# split_node_02.net
KiCad netlist of a schematic drawn in EAGLE
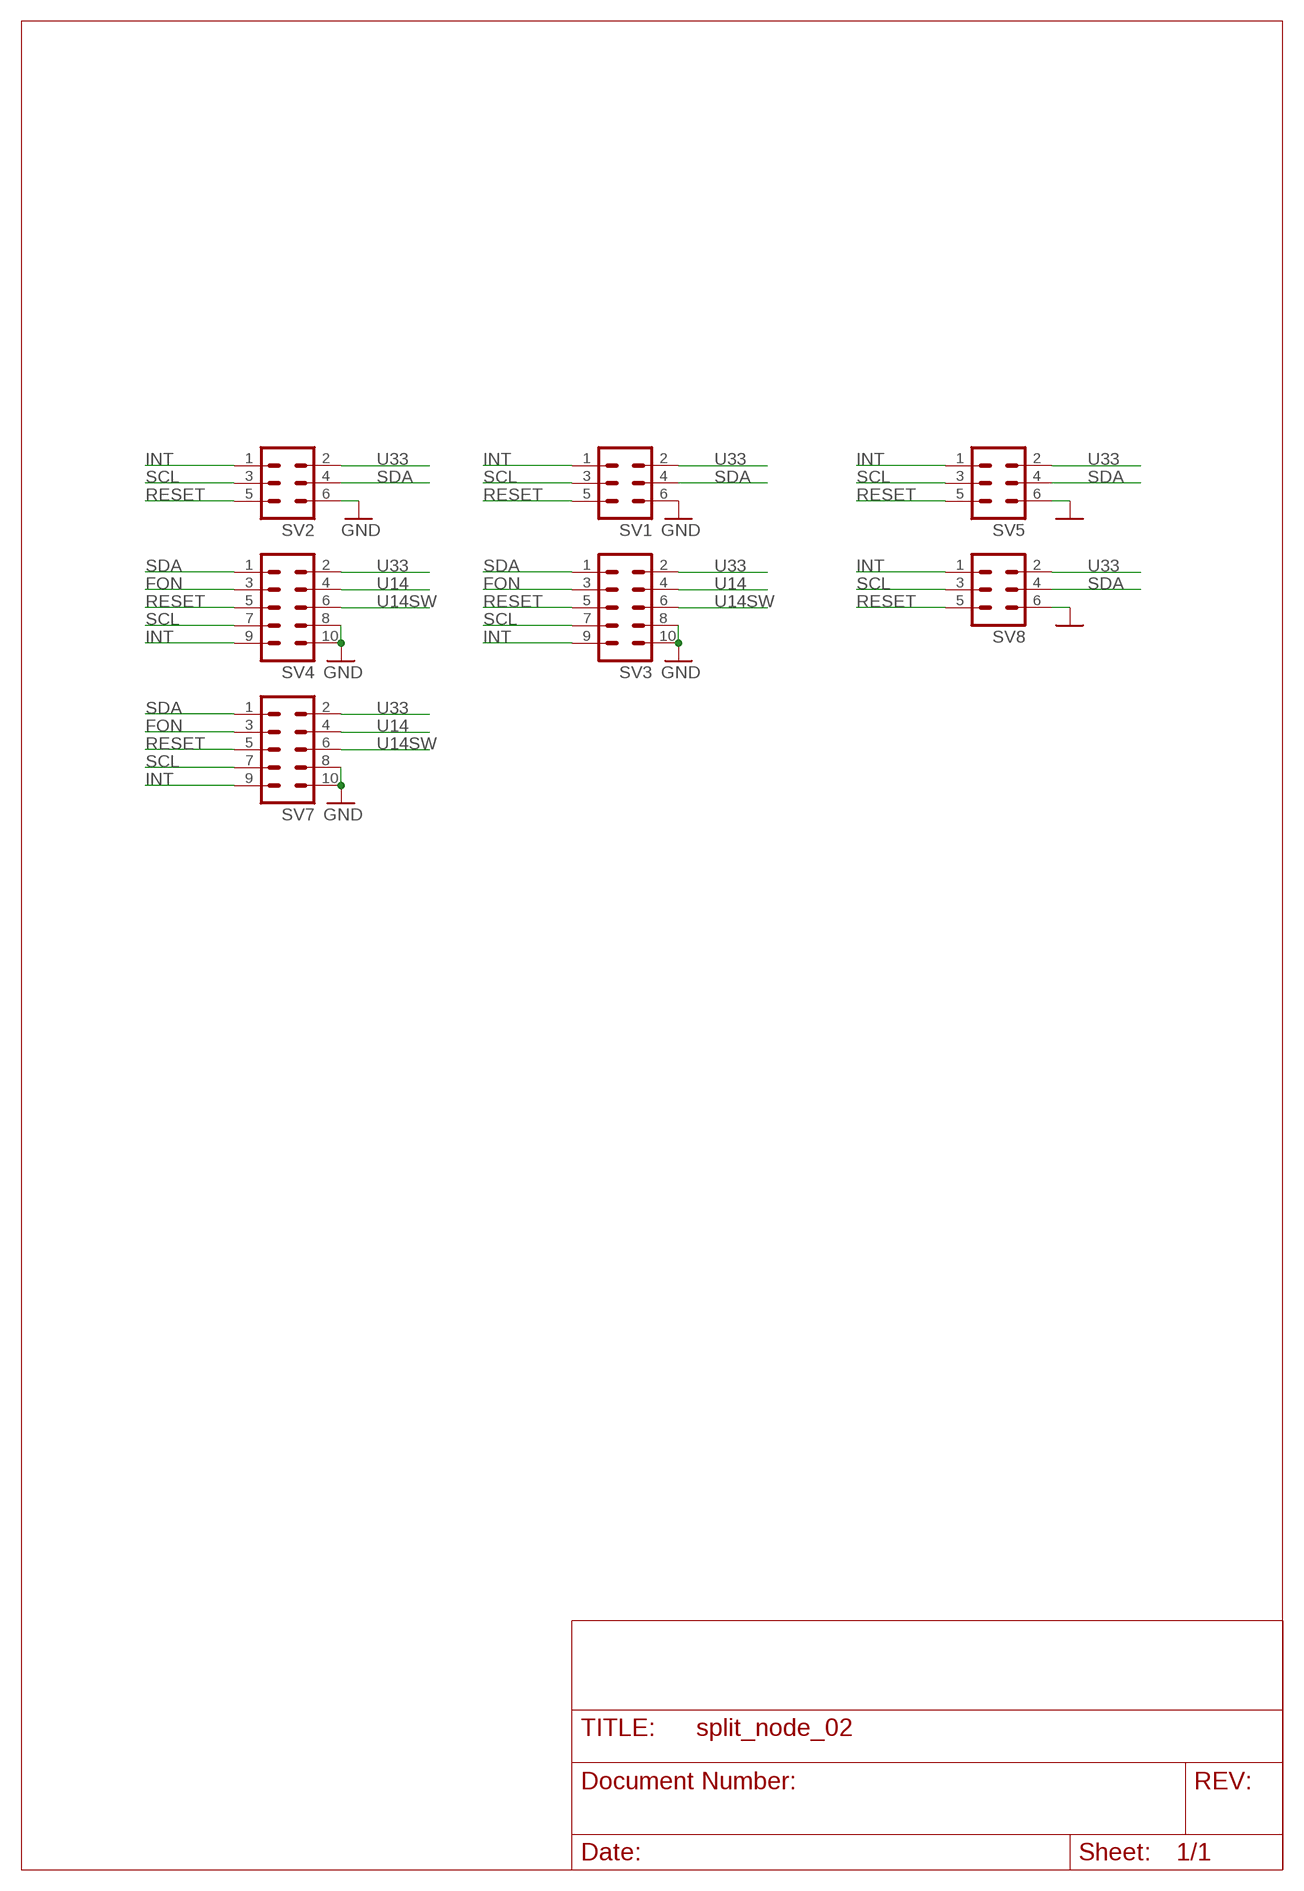
[diagram p0: schematic, sheet 1]

(export (version "E")
  (design (tool "Eeschema 10.0.6"))
  (components
    (comp (ref "SV1")
      (value "ML6")
      (footprint "eagle-import:ML6")
      (libsource (lib "eagle-import") (part "ML6"))
    )
    (comp (ref "SV2")
      (value "ML6")
      (footprint "eagle-import:ML6")
      (libsource (lib "eagle-import") (part "ML6"))
    )
    (comp (ref "SV3")
      (value "ML10")
      (footprint "eagle-import:ML10")
      (libsource (lib "eagle-import") (part "ML10"))
    )
    (comp (ref "SV4")
      (value "ML10")
      (footprint "eagle-import:ML10")
      (libsource (lib "eagle-import") (part "ML10"))
    )
    (comp (ref "SV5")
      (value "ML6")
      (footprint "eagle-import:ML6")
      (libsource (lib "eagle-import") (part "ML6"))
    )
    (comp (ref "SV7")
      (value "ML10")
      (footprint "eagle-import:ML10")
      (libsource (lib "eagle-import") (part "ML10"))
    )
    (comp (ref "SV8")
      (value "ML6")
      (footprint "eagle-import:ML6")
      (libsource (lib "eagle-import") (part "ML6"))
    )
  )
  (nets
    (net (code "1") (name "/FON") (class "Default")
      (node (ref "SV3") (pin "3") (pinfunction "3_3") (pintype "passive"))
      (node (ref "SV4") (pin "3") (pinfunction "3_3") (pintype "passive"))
      (node (ref "SV7") (pin "3") (pinfunction "3_3") (pintype "passive"))
    )
    (net (code "2") (name "/INT") (class "Default")
      (node (ref "SV1") (pin "1") (pinfunction "1_1") (pintype "passive"))
      (node (ref "SV2") (pin "1") (pinfunction "1_1") (pintype "passive"))
      (node (ref "SV3") (pin "9") (pinfunction "9_9") (pintype "passive"))
      (node (ref "SV4") (pin "9") (pinfunction "9_9") (pintype "passive"))
      (node (ref "SV5") (pin "1") (pinfunction "1_1") (pintype "passive"))
      (node (ref "SV7") (pin "9") (pinfunction "9_9") (pintype "passive"))
      (node (ref "SV8") (pin "1") (pinfunction "1_1") (pintype "passive"))
    )
    (net (code "3") (name "/RESET") (class "Default")
      (node (ref "SV1") (pin "5") (pinfunction "5_5") (pintype "passive"))
      (node (ref "SV2") (pin "5") (pinfunction "5_5") (pintype "passive"))
      (node (ref "SV3") (pin "5") (pinfunction "5_5") (pintype "passive"))
      (node (ref "SV4") (pin "5") (pinfunction "5_5") (pintype "passive"))
      (node (ref "SV5") (pin "5") (pinfunction "5_5") (pintype "passive"))
      (node (ref "SV7") (pin "5") (pinfunction "5_5") (pintype "passive"))
      (node (ref "SV8") (pin "5") (pinfunction "5_5") (pintype "passive"))
    )
    (net (code "4") (name "/SCL") (class "Default")
      (node (ref "SV1") (pin "3") (pinfunction "3_3") (pintype "passive"))
      (node (ref "SV2") (pin "3") (pinfunction "3_3") (pintype "passive"))
      (node (ref "SV3") (pin "7") (pinfunction "7_7") (pintype "passive"))
      (node (ref "SV4") (pin "7") (pinfunction "7_7") (pintype "passive"))
      (node (ref "SV5") (pin "3") (pinfunction "3_3") (pintype "passive"))
      (node (ref "SV7") (pin "7") (pinfunction "7_7") (pintype "passive"))
      (node (ref "SV8") (pin "3") (pinfunction "3_3") (pintype "passive"))
    )
    (net (code "5") (name "/SDA") (class "Default")
      (node (ref "SV1") (pin "4") (pinfunction "4_4") (pintype "passive"))
      (node (ref "SV2") (pin "4") (pinfunction "4_4") (pintype "passive"))
      (node (ref "SV3") (pin "1") (pinfunction "1_1") (pintype "passive"))
      (node (ref "SV4") (pin "1") (pinfunction "1_1") (pintype "passive"))
      (node (ref "SV5") (pin "4") (pinfunction "4_4") (pintype "passive"))
      (node (ref "SV7") (pin "1") (pinfunction "1_1") (pintype "passive"))
      (node (ref "SV8") (pin "4") (pinfunction "4_4") (pintype "passive"))
    )
    (net (code "6") (name "/U14") (class "Default")
      (node (ref "SV3") (pin "4") (pinfunction "4_4") (pintype "passive"))
      (node (ref "SV4") (pin "4") (pinfunction "4_4") (pintype "passive"))
      (node (ref "SV7") (pin "4") (pinfunction "4_4") (pintype "passive"))
    )
    (net (code "7") (name "/U14SW") (class "Default")
      (node (ref "SV3") (pin "6") (pinfunction "6_6") (pintype "passive"))
      (node (ref "SV4") (pin "6") (pinfunction "6_6") (pintype "passive"))
      (node (ref "SV7") (pin "6") (pinfunction "6_6") (pintype "passive"))
    )
    (net (code "8") (name "/U33") (class "Default")
      (node (ref "SV1") (pin "2") (pinfunction "2_2") (pintype "passive"))
      (node (ref "SV2") (pin "2") (pinfunction "2_2") (pintype "passive"))
      (node (ref "SV3") (pin "2") (pinfunction "2_2") (pintype "passive"))
      (node (ref "SV4") (pin "2") (pinfunction "2_2") (pintype "passive"))
      (node (ref "SV5") (pin "2") (pinfunction "2_2") (pintype "passive"))
      (node (ref "SV7") (pin "2") (pinfunction "2_2") (pintype "passive"))
      (node (ref "SV8") (pin "2") (pinfunction "2_2") (pintype "passive"))
    )
    (net (code "9") (name "GND") (class "Default")
      (node (ref "SV1") (pin "6") (pinfunction "6_6") (pintype "passive"))
      (node (ref "SV2") (pin "6") (pinfunction "6_6") (pintype "passive"))
      (node (ref "SV3") (pin "10") (pinfunction "10_10") (pintype "passive"))
      (node (ref "SV3") (pin "8") (pinfunction "8_8") (pintype "passive"))
      (node (ref "SV4") (pin "10") (pinfunction "10_10") (pintype "passive"))
      (node (ref "SV4") (pin "8") (pinfunction "8_8") (pintype "passive"))
      (node (ref "SV5") (pin "6") (pinfunction "6_6") (pintype "passive"))
      (node (ref "SV7") (pin "10") (pinfunction "10_10") (pintype "passive"))
      (node (ref "SV7") (pin "8") (pinfunction "8_8") (pintype "passive"))
      (node (ref "SV8") (pin "6") (pinfunction "6_6") (pintype "passive"))
    )
  )
)
